# 2_MPC555.net
KiCad netlist of a schematic drawn in Altium Designer
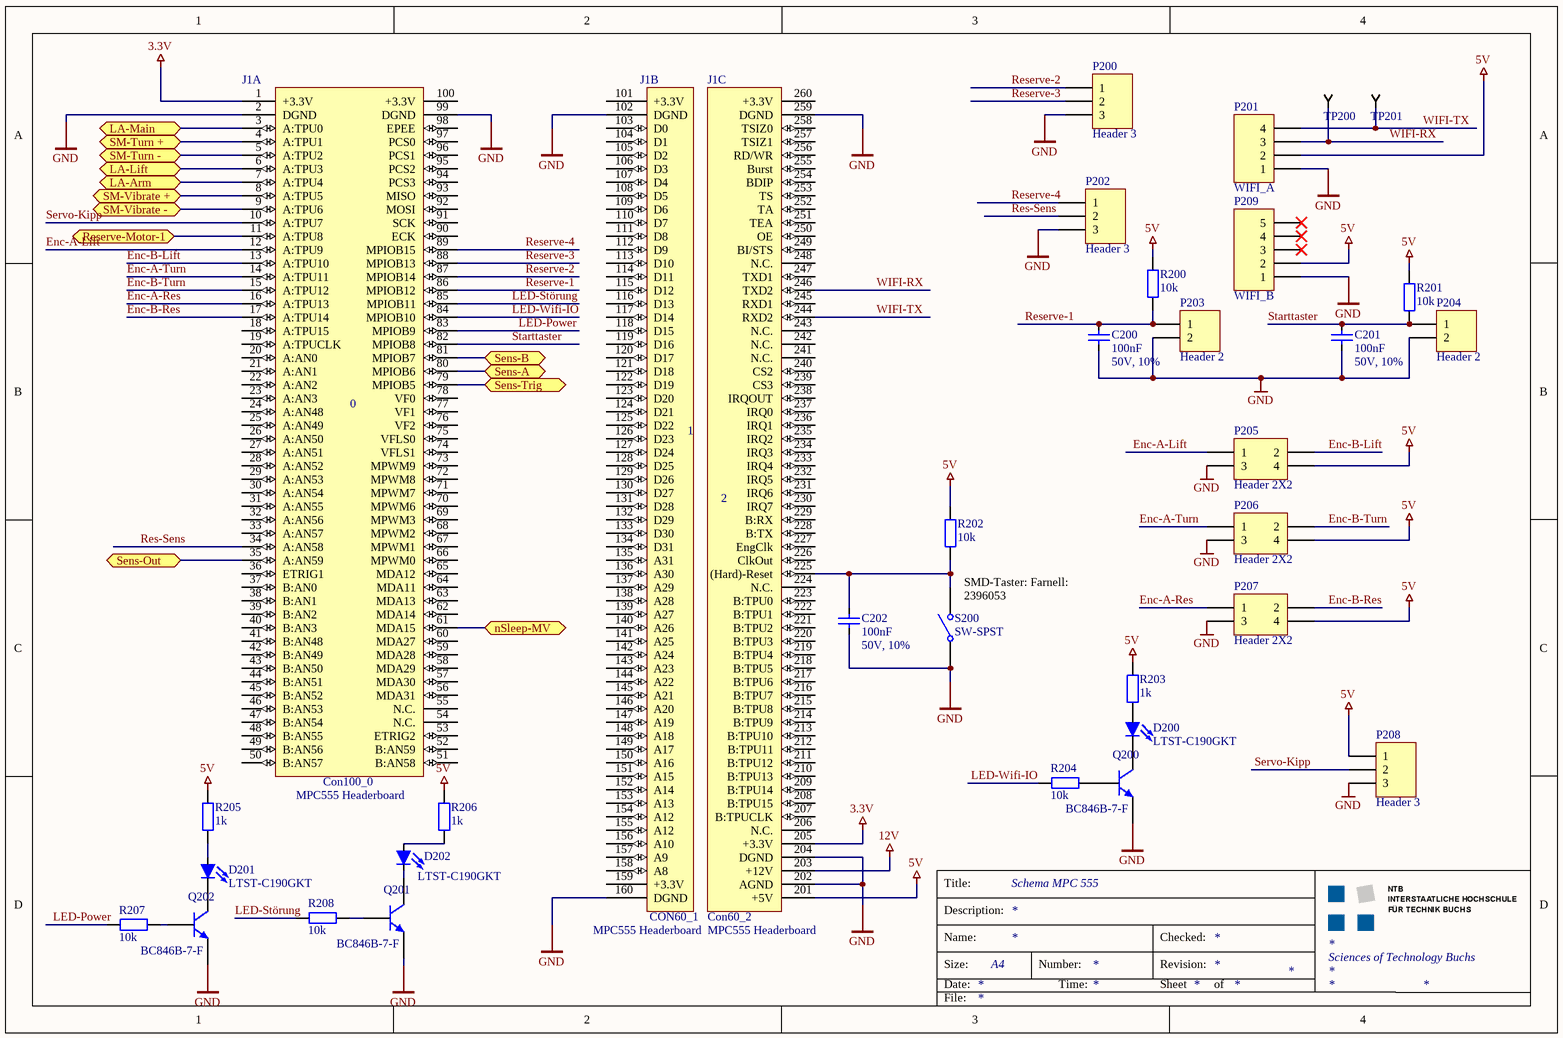
[diagram p0: 2_MPC555.SchDoc]

(export (version "E")
  (design (tool "Eeschema 10.0.6"))
  (components
    (comp (ref "C200")
      (value "100nF")
      (footprint "CAP-0805[2012]")
      (description "100n 50V X7R MLCC 0805 (1608 Metric)")
      (fields (field (name "TOLERANCE") "10%") (field (name "VALADDON") "50V, 10%"))
      (libsource (lib "IR-Sensor") (part "MLCC 0805 100n 50V"))
    )
    (comp (ref "C201")
      (value "100nF")
      (footprint "CAP-0805[2012]")
      (description "100n 50V X7R MLCC 0805 (1608 Metric)")
      (fields (field (name "TOLERANCE") "10%") (field (name "VALADDON") "50V, 10%"))
      (libsource (lib "IR-Sensor") (part "MLCC 0805 100n 50V"))
    )
    (comp (ref "C202")
      (value "100nF")
      (footprint "CAP-0805[2012]")
      (description "100n 50V X7R MLCC 0805 (1608 Metric)")
      (fields (field (name "TOLERANCE") "10%") (field (name "VALADDON") "50V, 10%"))
      (libsource (lib "IR-Sensor") (part "MLCC 0805 100n 50V"))
    )
    (comp (ref "D200")
      (value "LTST-C190GKT")
      (footprint "LED 0603 green")
      (description "LED SMD 0603 green 6mcd")
      (libsource (lib "IR-Sensor") (part "LED Green"))
    )
    (comp (ref "D201")
      (value "LTST-C190GKT")
      (footprint "LED 0603 green")
      (description "LED SMD 0603 green 6mcd")
      (libsource (lib "IR-Sensor") (part "LED Green"))
    )
    (comp (ref "D202")
      (value "LTST-C190GKT")
      (footprint "LED 0603 green")
      (description "LED SMD 0603 green 6mcd")
      (libsource (lib "IR-Sensor") (part "LED Green"))
    )
    (comp (ref "J1")
      (value "MPC555 Headerboard")
      (footprint "MPC555 Headerboard THT")
      (description "NTB MPC555 Headerboard")
      (libsource (lib "ch.ntb.inf.altiumlib_2011-02-10") (part "MPC555 Headerboard"))
    )
    (comp (ref "P200")
      (value "Header 3")
      (footprint "HDR1X3")
      (description "Header, 3-Pin")
      (fields (field (name "PUBLISHER") "Altium Limited"))
      (libsource (lib "Miscellaneous Connectors") (part "Header 3"))
    )
    (comp (ref "P201")
      (value "WIFI_A")
      (footprint "HDR1X4")
      (description "Header, 4-Pin")
      (fields (field (name "PUBLISHER") "Altium Limited"))
      (libsource (lib "Miscellaneous Connectors") (part "Header 4"))
    )
    (comp (ref "P202")
      (value "Header 3")
      (footprint "HDR1X3")
      (description "Header, 3-Pin")
      (fields (field (name "PUBLISHER") "Altium Limited"))
      (libsource (lib "Miscellaneous Connectors") (part "Header 3"))
    )
    (comp (ref "P203")
      (value "Header 2")
      (footprint "HDR1X2")
      (description "Header, 2-Pin")
      (fields (field (name "PUBLISHER") "Altium Limited"))
      (libsource (lib "Miscellaneous Connectors") (part "Header 2"))
    )
    (comp (ref "P204")
      (value "Header 2")
      (footprint "HDR1X2")
      (description "Header, 2-Pin")
      (fields (field (name "PUBLISHER") "Altium Limited"))
      (libsource (lib "Miscellaneous Connectors") (part "Header 2"))
    )
    (comp (ref "P205")
      (value "Header 2X2")
      (footprint "HDR2X2")
      (description "Header, 2-Pin, Dual row")
      (fields (field (name "PUBLISHER") "Altium Limited"))
      (libsource (lib "Miscellaneous Connectors") (part "Header 2X2"))
    )
    (comp (ref "P206")
      (value "Header 2X2")
      (footprint "HDR2X2")
      (description "Header, 2-Pin, Dual row")
      (fields (field (name "PUBLISHER") "Altium Limited"))
      (libsource (lib "Miscellaneous Connectors") (part "Header 2X2"))
    )
    (comp (ref "P207")
      (value "Header 2X2")
      (footprint "HDR2X2")
      (description "Header, 2-Pin, Dual row")
      (fields (field (name "PUBLISHER") "Altium Limited"))
      (libsource (lib "Miscellaneous Connectors") (part "Header 2X2"))
    )
    (comp (ref "P208")
      (value "Header 3")
      (footprint "HDR1X3")
      (description "Header, 3-Pin")
      (fields (field (name "PUBLISHER") "Altium Limited"))
      (libsource (lib "Miscellaneous Connectors") (part "Header 3"))
    )
    (comp (ref "P209")
      (value "WIFI_B")
      (footprint "HDR1X5")
      (description "Header, 5-Pin")
      (fields (field (name "PUBLISHER") "Altium Limited"))
      (libsource (lib "Miscellaneous Connectors") (part "Header 5"))
    )
    (comp (ref "Q200")
      (value "BC846B-7-F")
      (footprint "SOT-23")
      (description "NPN General-purpose Transistor")
      (fields (field (name "MANUFACTURER") "DIODES INC") (field (name "PUBLISHER") "Altium Limited"))
      (libsource (lib "IR-Sensor") (part "BC846B-SOT23"))
    )
    (comp (ref "Q201")
      (value "BC846B-7-F")
      (footprint "SOT-23")
      (description "NPN General-purpose Transistor")
      (fields (field (name "MANUFACTURER") "DIODES INC") (field (name "PUBLISHER") "Altium Limited"))
      (libsource (lib "IR-Sensor") (part "BC846B-SOT23"))
    )
    (comp (ref "Q202")
      (value "BC846B-7-F")
      (footprint "SOT-23")
      (description "NPN General-purpose Transistor")
      (fields (field (name "MANUFACTURER") "DIODES INC") (field (name "PUBLISHER") "Altium Limited"))
      (libsource (lib "IR-Sensor") (part "BC846B-SOT23"))
    )
    (comp (ref "R200")
      (value "10k")
      (footprint "RES-0805[2012]")
      (description "0805 (2013 Metric) 1/10 W 10K 1 Thick Film Chip Resistor")
      (fields (field (name "POWER") "1/10 W") (field (name "TOLERANCE") "1%"))
      (libsource (lib "IR-Sensor") (part "RES 0805"))
    )
    (comp (ref "R201")
      (value "10k")
      (footprint "RES-0805[2012]")
      (description "0805 (2013 Metric) 1/10 W 10K 1 Thick Film Chip Resistor")
      (fields (field (name "POWER") "1/10 W") (field (name "TOLERANCE") "1%"))
      (libsource (lib "IR-Sensor") (part "RES 0805"))
    )
    (comp (ref "R202")
      (value "10k")
      (footprint "RES-0805[2012]")
      (description "0805 (2013 Metric) 1/10 W 10K 1 Thick Film Chip Resistor")
      (fields (field (name "POWER") "1/10 W") (field (name "TOLERANCE") "1%"))
      (libsource (lib "IR-Sensor") (part "RES 0805"))
    )
    (comp (ref "R203")
      (value "1k")
      (footprint "RES-0805[2012]")
      (description "0805 (2013 Metric) 1/10 W 10K 1 Thick Film Chip Resistor")
      (fields (field (name "POWER") "1/10 W") (field (name "TOLERANCE") "1%"))
      (libsource (lib "IR-Sensor") (part "RES 0805"))
    )
    (comp (ref "R204")
      (value "10k")
      (footprint "RES-0805[2012]")
      (description "0805 (2013 Metric) 1/10 W 10K 1 Thick Film Chip Resistor")
      (fields (field (name "POWER") "1/10 W") (field (name "TOLERANCE") "1%"))
      (libsource (lib "IR-Sensor") (part "RES 0805"))
    )
    (comp (ref "R205")
      (value "1k")
      (footprint "RES-0805[2012]")
      (description "0805 (2013 Metric) 1/10 W 10K 1 Thick Film Chip Resistor")
      (fields (field (name "POWER") "1/10 W") (field (name "TOLERANCE") "1%"))
      (libsource (lib "IR-Sensor") (part "RES 0805"))
    )
    (comp (ref "R206")
      (value "1k")
      (footprint "RES-0805[2012]")
      (description "0805 (2013 Metric) 1/10 W 10K 1 Thick Film Chip Resistor")
      (fields (field (name "POWER") "1/10 W") (field (name "TOLERANCE") "1%"))
      (libsource (lib "IR-Sensor") (part "RES 0805"))
    )
    (comp (ref "R207")
      (value "10k")
      (footprint "RES-0805[2012]")
      (description "0805 (2013 Metric) 1/10 W 10K 1 Thick Film Chip Resistor")
      (fields (field (name "POWER") "1/10 W") (field (name "TOLERANCE") "1%"))
      (libsource (lib "IR-Sensor") (part "RES 0805"))
    )
    (comp (ref "R208")
      (value "10k")
      (footprint "RES-0805[2012]")
      (description "0805 (2013 Metric) 1/10 W 10K 1 Thick Film Chip Resistor")
      (fields (field (name "POWER") "1/10 W") (field (name "TOLERANCE") "1%"))
      (libsource (lib "IR-Sensor") (part "RES 0805"))
    )
    (comp (ref "S200")
      (value "SW-SPST")
      (footprint "B3SE-1002P")
      (description "Single-Pole, Single-Throw Switch")
      (fields (field (name "PUBLISHER") "Altium Limited"))
      (libsource (lib "Miscellaneous Devices") (part "SW-SPST"))
    )
    (comp (ref "TP200")
      (value "Testpoint SMD 1206")
      (footprint "TP-SMD-1206")
      (description "Testpoint xSmall")
      (libsource (lib "IR-Sensor") (part "Testpoint SMD 1206"))
    )
    (comp (ref "TP201")
      (value "Testpoint SMD 1206")
      (footprint "TP-SMD-1206")
      (description "Testpoint xSmall")
      (libsource (lib "IR-Sensor") (part "Testpoint SMD 1206"))
    )
  )
  (nets
    (net (code "1") (name "/Enc-A-Lift") (class "Default")
      (node (ref "J1") (pin "12") (pinfunction "A:TPU9_12") (pintype "bidirectional"))
      (node (ref "P205") (pin "1") (pinfunction "1_1") (pintype "passive"))
    )
    (net (code "2") (name "/Enc-A-Res") (class "Default")
      (node (ref "J1") (pin "16") (pinfunction "A:TPU13_16") (pintype "bidirectional"))
      (node (ref "P207") (pin "1") (pinfunction "1_1") (pintype "passive"))
    )
    (net (code "3") (name "/Enc-A-Turn") (class "Default")
      (node (ref "J1") (pin "14") (pinfunction "A:TPU11_14") (pintype "bidirectional"))
      (node (ref "P206") (pin "1") (pinfunction "1_1") (pintype "passive"))
    )
    (net (code "4") (name "/Enc-B-Lift") (class "Default")
      (node (ref "J1") (pin "13") (pinfunction "A:TPU10_13") (pintype "bidirectional"))
      (node (ref "P205") (pin "2") (pinfunction "2_2") (pintype "passive"))
    )
    (net (code "5") (name "/Enc-B-Res") (class "Default")
      (node (ref "J1") (pin "17") (pinfunction "A:TPU14_17") (pintype "bidirectional"))
      (node (ref "P207") (pin "2") (pinfunction "2_2") (pintype "passive"))
    )
    (net (code "6") (name "/Enc-B-Turn") (class "Default")
      (node (ref "J1") (pin "15") (pinfunction "A:TPU12_15") (pintype "bidirectional"))
      (node (ref "P206") (pin "2") (pinfunction "2_2") (pintype "passive"))
    )
    (net (code "7") (name "/LA-Arm") (class "Default")
      (node (ref "J1") (pin "7") (pinfunction "A:TPU4_7") (pintype "bidirectional"))
    )
    (net (code "8") (name "/LA-Lift") (class "Default")
      (node (ref "J1") (pin "6") (pinfunction "A:TPU3_6") (pintype "bidirectional"))
    )
    (net (code "9") (name "/LA-Main") (class "Default")
      (node (ref "J1") (pin "3") (pinfunction "A:TPU0_3") (pintype "bidirectional"))
    )
    (net (code "10") (name "/LED-Power") (class "Default")
      (node (ref "J1") (pin "83") (pinfunction "MPIOB9_83") (pintype "bidirectional"))
      (node (ref "R207") (pin "1") (pinfunction "1_1") (pintype "passive"))
    )
    (net (code "11") (name "/LED-Störung") (class "Default")
      (node (ref "J1") (pin "85") (pinfunction "MPIOB11_85") (pintype "bidirectional"))
      (node (ref "R208") (pin "1") (pinfunction "1_1") (pintype "passive"))
    )
    (net (code "12") (name "/LED-Wifi-IO") (class "Default")
      (node (ref "J1") (pin "84") (pinfunction "MPIOB10_84") (pintype "bidirectional"))
      (node (ref "R204") (pin "1") (pinfunction "1_1") (pintype "passive"))
    )
    (net (code "13") (name "/Res-Sens") (class "Default")
      (node (ref "J1") (pin "34") (pinfunction "A:AN58_34") (pintype "bidirectional"))
      (node (ref "P202") (pin "2") (pinfunction "2_2") (pintype "passive"))
    )
    (net (code "14") (name "/Reserve-1") (class "Default")
      (node (ref "C200") (pin "2") (pinfunction "Neg_2") (pintype "passive"))
      (node (ref "J1") (pin "86") (pinfunction "MPIOB12_86") (pintype "bidirectional"))
      (node (ref "P203") (pin "1") (pinfunction "1_1") (pintype "passive"))
      (node (ref "R200") (pin "1") (pinfunction "1_1") (pintype "passive"))
    )
    (net (code "15") (name "/Reserve-2") (class "Default")
      (node (ref "J1") (pin "87") (pinfunction "MPIOB14_87") (pintype "bidirectional"))
      (node (ref "P200") (pin "1") (pinfunction "1_1") (pintype "passive"))
    )
    (net (code "16") (name "/Reserve-3") (class "Default")
      (node (ref "J1") (pin "88") (pinfunction "MPIOB13_88") (pintype "bidirectional"))
      (node (ref "P200") (pin "2") (pinfunction "2_2") (pintype "passive"))
    )
    (net (code "17") (name "/Reserve-4") (class "Default")
      (node (ref "J1") (pin "89") (pinfunction "MPIOB15_89") (pintype "bidirectional"))
      (node (ref "P202") (pin "1") (pinfunction "1_1") (pintype "passive"))
    )
    (net (code "18") (name "/Reserve-Motor-1") (class "Default")
      (node (ref "J1") (pin "11") (pinfunction "A:TPU8_11") (pintype "bidirectional"))
    )
    (net (code "19") (name "/SM-Turn +") (class "Default")
      (node (ref "J1") (pin "4") (pinfunction "A:TPU1_4") (pintype "bidirectional"))
    )
    (net (code "20") (name "/SM-Turn -") (class "Default")
      (node (ref "J1") (pin "5") (pinfunction "A:TPU2_5") (pintype "bidirectional"))
    )
    (net (code "21") (name "/SM-Vibrate +") (class "Default")
      (node (ref "J1") (pin "8") (pinfunction "A:TPU5_8") (pintype "bidirectional"))
    )
    (net (code "22") (name "/SM-Vibrate -") (class "Default")
      (node (ref "J1") (pin "9") (pinfunction "A:TPU6_9") (pintype "bidirectional"))
    )
    (net (code "23") (name "/Sens-A") (class "Default")
      (node (ref "J1") (pin "80") (pinfunction "MPIOB6_80") (pintype "bidirectional"))
    )
    (net (code "24") (name "/Sens-B") (class "Default")
      (node (ref "J1") (pin "81") (pinfunction "MPIOB7_81") (pintype "bidirectional"))
    )
    (net (code "25") (name "/Sens-Out") (class "Default")
      (node (ref "J1") (pin "35") (pinfunction "A:AN59_35") (pintype "bidirectional"))
    )
    (net (code "26") (name "/Sens-Trig") (class "Default")
      (node (ref "J1") (pin "79") (pinfunction "MPIOB5_79") (pintype "bidirectional"))
    )
    (net (code "27") (name "/Servo-Kipp") (class "Default")
      (node (ref "J1") (pin "10") (pinfunction "A:TPU7_10") (pintype "bidirectional"))
      (node (ref "P208") (pin "2") (pinfunction "2_2") (pintype "passive"))
    )
    (net (code "28") (name "/Starttaster") (class "Default")
      (node (ref "C201") (pin "2") (pinfunction "Neg_2") (pintype "passive"))
      (node (ref "J1") (pin "82") (pinfunction "MPIOB8_82") (pintype "bidirectional"))
      (node (ref "P204") (pin "1") (pinfunction "1_1") (pintype "passive"))
      (node (ref "R201") (pin "1") (pinfunction "1_1") (pintype "passive"))
    )
    (net (code "29") (name "/WIFI-RX") (class "Default")
      (node (ref "J1") (pin "246") (pinfunction "TXD2_246") (pintype "bidirectional"))
      (node (ref "P201") (pin "3") (pinfunction "3_3") (pintype "passive"))
      (node (ref "TP200") (pin "1") (pinfunction "0_1") (pintype "passive"))
    )
    (net (code "30") (name "/WIFI-TX") (class "Default")
      (node (ref "J1") (pin "244") (pinfunction "RXD2_244") (pintype "bidirectional"))
      (node (ref "P201") (pin "4") (pinfunction "4_4") (pintype "passive"))
      (node (ref "TP201") (pin "1") (pinfunction "0_1") (pintype "passive"))
    )
    (net (code "31") (name "/nSleep-MV") (class "Default")
      (node (ref "J1") (pin "61") (pinfunction "MDA15_61") (pintype "bidirectional"))
    )
    (net (code "32") (name "3.3V") (class "Default")
      (node (ref "J1") (pin "1") (pinfunction "+3.3V_1") (pintype "power_in"))
      (node (ref "J1") (pin "205") (pinfunction "+3.3V_205") (pintype "power_in"))
    )
    (net (code "33") (name "5V") (class "Default")
      (node (ref "J1") (pin "201") (pinfunction "+5V_201") (pintype "power_in"))
      (node (ref "P201") (pin "2") (pinfunction "2_2") (pintype "passive"))
      (node (ref "P205") (pin "4") (pinfunction "4_4") (pintype "passive"))
      (node (ref "P206") (pin "4") (pinfunction "4_4") (pintype "passive"))
      (node (ref "P207") (pin "4") (pinfunction "4_4") (pintype "passive"))
      (node (ref "P208") (pin "1") (pinfunction "1_1") (pintype "passive"))
      (node (ref "P209") (pin "2") (pinfunction "2_2") (pintype "passive"))
      (node (ref "R200") (pin "2") (pinfunction "2_2") (pintype "passive"))
      (node (ref "R201") (pin "2") (pinfunction "2_2") (pintype "passive"))
      (node (ref "R202") (pin "2") (pinfunction "2_2") (pintype "passive"))
      (node (ref "R203") (pin "2") (pinfunction "2_2") (pintype "passive"))
      (node (ref "R205") (pin "2") (pinfunction "2_2") (pintype "passive"))
      (node (ref "R206") (pin "2") (pinfunction "2_2") (pintype "passive"))
    )
    (net (code "34") (name "12V") (class "Default")
      (node (ref "J1") (pin "203") (pinfunction "+12V_203") (pintype "power_in"))
    )
    (net (code "35") (name "GND") (class "Default")
      (node (ref "C200") (pin "1") (pinfunction "Pos_1") (pintype "passive"))
      (node (ref "C201") (pin "1") (pinfunction "Pos_1") (pintype "passive"))
      (node (ref "C202") (pin "1") (pinfunction "Pos_1") (pintype "passive"))
      (node (ref "J1") (pin "102") (pinfunction "DGND_102") (pintype "power_in"))
      (node (ref "J1") (pin "160") (pinfunction "DGND_160") (pintype "power_in"))
      (node (ref "J1") (pin "2") (pinfunction "DGND_2") (pintype "power_in"))
      (node (ref "J1") (pin "202") (pinfunction "AGND_202") (pintype "power_in"))
      (node (ref "J1") (pin "204") (pinfunction "DGND_204") (pintype "power_in"))
      (node (ref "J1") (pin "259") (pinfunction "DGND_259") (pintype "power_in"))
      (node (ref "J1") (pin "99") (pinfunction "DGND_99") (pintype "power_in"))
      (node (ref "P200") (pin "3") (pinfunction "3_3") (pintype "passive"))
      (node (ref "P201") (pin "1") (pinfunction "1_1") (pintype "passive"))
      (node (ref "P202") (pin "3") (pinfunction "3_3") (pintype "passive"))
      (node (ref "P203") (pin "2") (pinfunction "2_2") (pintype "passive"))
      (node (ref "P204") (pin "2") (pinfunction "2_2") (pintype "passive"))
      (node (ref "P205") (pin "3") (pinfunction "3_3") (pintype "passive"))
      (node (ref "P206") (pin "3") (pinfunction "3_3") (pintype "passive"))
      (node (ref "P207") (pin "3") (pinfunction "3_3") (pintype "passive"))
      (node (ref "P208") (pin "3") (pinfunction "3_3") (pintype "passive"))
      (node (ref "P209") (pin "1") (pinfunction "1_1") (pintype "passive"))
      (node (ref "Q200") (pin "2") (pinfunction "E_2") (pintype "passive"))
      (node (ref "Q201") (pin "2") (pinfunction "E_2") (pintype "passive"))
      (node (ref "Q202") (pin "2") (pinfunction "E_2") (pintype "passive"))
      (node (ref "S200") (pin "1") (pinfunction "COMMON_1") (pintype "passive"))
    )
    (net (code "36") (name "Net-(C202-Neg)") (class "Default")
      (node (ref "C202") (pin "2") (pinfunction "Neg_2") (pintype "passive"))
      (node (ref "J1") (pin "225") (pinfunction "(Hard)-Reset_225") (pintype "bidirectional"))
      (node (ref "R202") (pin "1") (pinfunction "1_1") (pintype "passive"))
      (node (ref "S200") (pin "2") (pinfunction "NO_2") (pintype "passive"))
    )
    (net (code "37") (name "Net-(D200-A)") (class "Default")
      (node (ref "D200") (pin "2") (pinfunction "A_2") (pintype "passive"))
      (node (ref "R203") (pin "1") (pinfunction "1_1") (pintype "passive"))
    )
    (net (code "38") (name "Net-(D200-K)") (class "Default")
      (node (ref "D200") (pin "1") (pinfunction "K_1") (pintype "passive"))
      (node (ref "Q200") (pin "3") (pinfunction "C_3") (pintype "passive"))
    )
    (net (code "39") (name "Net-(D201-A)") (class "Default")
      (node (ref "D201") (pin "2") (pinfunction "A_2") (pintype "passive"))
      (node (ref "R205") (pin "1") (pinfunction "1_1") (pintype "passive"))
    )
    (net (code "40") (name "Net-(D201-K)") (class "Default")
      (node (ref "D201") (pin "1") (pinfunction "K_1") (pintype "passive"))
      (node (ref "Q202") (pin "3") (pinfunction "C_3") (pintype "passive"))
    )
    (net (code "41") (name "Net-(D202-A)") (class "Default")
      (node (ref "D202") (pin "2") (pinfunction "A_2") (pintype "passive"))
      (node (ref "R206") (pin "1") (pinfunction "1_1") (pintype "passive"))
    )
    (net (code "42") (name "Net-(D202-K)") (class "Default")
      (node (ref "D202") (pin "1") (pinfunction "K_1") (pintype "passive"))
      (node (ref "Q201") (pin "3") (pinfunction "C_3") (pintype "passive"))
    )
    (net (code "43") (name "Net-(Q200-B)") (class "Default")
      (node (ref "Q200") (pin "1") (pinfunction "B_1") (pintype "passive"))
      (node (ref "R204") (pin "2") (pinfunction "2_2") (pintype "passive"))
    )
    (net (code "44") (name "Net-(Q201-B)") (class "Default")
      (node (ref "Q201") (pin "1") (pinfunction "B_1") (pintype "passive"))
      (node (ref "R208") (pin "2") (pinfunction "2_2") (pintype "passive"))
    )
    (net (code "45") (name "Net-(Q202-B)") (class "Default")
      (node (ref "Q202") (pin "1") (pinfunction "B_1") (pintype "passive"))
      (node (ref "R207") (pin "2") (pinfunction "2_2") (pintype "passive"))
    )
    (net (code "46") (name "unconnected-(J1A-+3.3V-Pad100)") (class "Default")
      (node (ref "J1") (pin "100") (pinfunction "+3.3V_100") (pintype "power_in"))
    )
    (net (code "47") (name "unconnected-(J1A-A:AN0-Pad20)") (class "Default")
      (node (ref "J1") (pin "20") (pinfunction "A:AN0_20") (pintype "bidirectional"))
    )
    (net (code "48") (name "unconnected-(J1A-A:AN1-Pad21)") (class "Default")
      (node (ref "J1") (pin "21") (pinfunction "A:AN1_21") (pintype "bidirectional"))
    )
    (net (code "49") (name "unconnected-(J1A-A:AN2-Pad22)") (class "Default")
      (node (ref "J1") (pin "22") (pinfunction "A:AN2_22") (pintype "bidirectional"))
    )
    (net (code "50") (name "unconnected-(J1A-A:AN3-Pad23)") (class "Default")
      (node (ref "J1") (pin "23") (pinfunction "A:AN3_23") (pintype "bidirectional"))
    )
    (net (code "51") (name "unconnected-(J1A-A:AN48-Pad24)") (class "Default")
      (node (ref "J1") (pin "24") (pinfunction "A:AN48_24") (pintype "bidirectional"))
    )
    (net (code "52") (name "unconnected-(J1A-A:AN49-Pad25)") (class "Default")
      (node (ref "J1") (pin "25") (pinfunction "A:AN49_25") (pintype "bidirectional"))
    )
    (net (code "53") (name "unconnected-(J1A-A:AN50-Pad26)") (class "Default")
      (node (ref "J1") (pin "26") (pinfunction "A:AN50_26") (pintype "bidirectional"))
    )
    (net (code "54") (name "unconnected-(J1A-A:AN51-Pad27)") (class "Default")
      (node (ref "J1") (pin "27") (pinfunction "A:AN51_27") (pintype "bidirectional"))
    )
    (net (code "55") (name "unconnected-(J1A-A:AN52-Pad28)") (class "Default")
      (node (ref "J1") (pin "28") (pinfunction "A:AN52_28") (pintype "bidirectional"))
    )
    (net (code "56") (name "unconnected-(J1A-A:AN53-Pad29)") (class "Default")
      (node (ref "J1") (pin "29") (pinfunction "A:AN53_29") (pintype "bidirectional"))
    )
    (net (code "57") (name "unconnected-(J1A-A:AN54-Pad30)") (class "Default")
      (node (ref "J1") (pin "30") (pinfunction "A:AN54_30") (pintype "bidirectional"))
    )
    (net (code "58") (name "unconnected-(J1A-A:AN55-Pad31)") (class "Default")
      (node (ref "J1") (pin "31") (pinfunction "A:AN55_31") (pintype "bidirectional"))
    )
    (net (code "59") (name "unconnected-(J1A-A:AN56-Pad32)") (class "Default")
      (node (ref "J1") (pin "32") (pinfunction "A:AN56_32") (pintype "bidirectional"))
    )
    (net (code "60") (name "unconnected-(J1A-A:AN57-Pad33)") (class "Default")
      (node (ref "J1") (pin "33") (pinfunction "A:AN57_33") (pintype "bidirectional"))
    )
    (net (code "61") (name "unconnected-(J1A-A:TPU15-Pad18)") (class "Default")
      (node (ref "J1") (pin "18") (pinfunction "A:TPU15_18") (pintype "bidirectional"))
    )
    (net (code "62") (name "unconnected-(J1A-A:TPUCLK-Pad19)") (class "Default")
      (node (ref "J1") (pin "19") (pinfunction "A:TPUCLK_19") (pintype "bidirectional"))
    )
    (net (code "63") (name "unconnected-(J1A-B:AN0-Pad37)") (class "Default")
      (node (ref "J1") (pin "37") (pinfunction "B:AN0_37") (pintype "bidirectional"))
    )
    (net (code "64") (name "unconnected-(J1A-B:AN1-Pad38)") (class "Default")
      (node (ref "J1") (pin "38") (pinfunction "B:AN1_38") (pintype "bidirectional"))
    )
    (net (code "65") (name "unconnected-(J1A-B:AN2-Pad39)") (class "Default")
      (node (ref "J1") (pin "39") (pinfunction "B:AN2_39") (pintype "bidirectional"))
    )
    (net (code "66") (name "unconnected-(J1A-B:AN3-Pad40)") (class "Default")
      (node (ref "J1") (pin "40") (pinfunction "B:AN3_40") (pintype "bidirectional"))
    )
    (net (code "67") (name "unconnected-(J1A-B:AN48-Pad41)") (class "Default")
      (node (ref "J1") (pin "41") (pinfunction "B:AN48_41") (pintype "bidirectional"))
    )
    (net (code "68") (name "unconnected-(J1A-B:AN49-Pad42)") (class "Default")
      (node (ref "J1") (pin "42") (pinfunction "B:AN49_42") (pintype "bidirectional"))
    )
    (net (code "69") (name "unconnected-(J1A-B:AN50-Pad43)") (class "Default")
      (node (ref "J1") (pin "43") (pinfunction "B:AN50_43") (pintype "bidirectional"))
    )
    (net (code "70") (name "unconnected-(J1A-B:AN51-Pad44)") (class "Default")
      (node (ref "J1") (pin "44") (pinfunction "B:AN51_44") (pintype "bidirectional"))
    )
    (net (code "71") (name "unconnected-(J1A-B:AN52-Pad45)") (class "Default")
      (node (ref "J1") (pin "45") (pinfunction "B:AN52_45") (pintype "bidirectional"))
    )
    (net (code "72") (name "unconnected-(J1A-B:AN53-Pad46)") (class "Default")
      (node (ref "J1") (pin "46") (pinfunction "B:AN53_46") (pintype "bidirectional"))
    )
    (net (code "73") (name "unconnected-(J1A-B:AN54-Pad47)") (class "Default")
      (node (ref "J1") (pin "47") (pinfunction "B:AN54_47") (pintype "bidirectional"))
    )
    (net (code "74") (name "unconnected-(J1A-B:AN55-Pad48)") (class "Default")
      (node (ref "J1") (pin "48") (pinfunction "B:AN55_48") (pintype "bidirectional"))
    )
    (net (code "75") (name "unconnected-(J1A-B:AN56-Pad49)") (class "Default")
      (node (ref "J1") (pin "49") (pinfunction "B:AN56_49") (pintype "bidirectional"))
    )
    (net (code "76") (name "unconnected-(J1A-B:AN57-Pad50)") (class "Default")
      (node (ref "J1") (pin "50") (pinfunction "B:AN57_50") (pintype "bidirectional"))
    )
    (net (code "77") (name "unconnected-(J1A-B:AN58-Pad51)") (class "Default")
      (node (ref "J1") (pin "51") (pinfunction "B:AN58_51") (pintype "bidirectional"))
    )
    (net (code "78") (name "unconnected-(J1A-B:AN59-Pad52)") (class "Default")
      (node (ref "J1") (pin "52") (pinfunction "B:AN59_52") (pintype "bidirectional"))
    )
    (net (code "79") (name "unconnected-(J1A-ECK-Pad90)") (class "Default")
      (node (ref "J1") (pin "90") (pinfunction "ECK_90") (pintype "bidirectional"))
    )
    (net (code "80") (name "unconnected-(J1A-EPEE-Pad98)") (class "Default")
      (node (ref "J1") (pin "98") (pinfunction "EPEE_98") (pintype "bidirectional"))
    )
    (net (code "81") (name "unconnected-(J1A-ETRIG1-Pad36)") (class "Default")
      (node (ref "J1") (pin "36") (pinfunction "ETRIG1_36") (pintype "bidirectional"))
    )
    (net (code "82") (name "unconnected-(J1A-ETRIG2-Pad53)") (class "Default")
      (node (ref "J1") (pin "53") (pinfunction "ETRIG2_53") (pintype "bidirectional"))
    )
    (net (code "83") (name "unconnected-(J1A-MDA11-Pad64)") (class "Default")
      (node (ref "J1") (pin "64") (pinfunction "MDA11_64") (pintype "bidirectional"))
    )
    (net (code "84") (name "unconnected-(J1A-MDA12-Pad65)") (class "Default")
      (node (ref "J1") (pin "65") (pinfunction "MDA12_65") (pintype "bidirectional"))
    )
    (net (code "85") (name "unconnected-(J1A-MDA13-Pad63)") (class "Default")
      (node (ref "J1") (pin "63") (pinfunction "MDA13_63") (pintype "bidirectional"))
    )
    (net (code "86") (name "unconnected-(J1A-MDA14-Pad62)") (class "Default")
      (node (ref "J1") (pin "62") (pinfunction "MDA14_62") (pintype "bidirectional"))
    )
    (net (code "87") (name "unconnected-(J1A-MDA27-Pad60)") (class "Default")
      (node (ref "J1") (pin "60") (pinfunction "MDA27_60") (pintype "bidirectional"))
    )
    (net (code "88") (name "unconnected-(J1A-MDA28-Pad59)") (class "Default")
      (node (ref "J1") (pin "59") (pinfunction "MDA28_59") (pintype "bidirectional"))
    )
    (net (code "89") (name "unconnected-(J1A-MDA29-Pad58)") (class "Default")
      (node (ref "J1") (pin "58") (pinfunction "MDA29_58") (pintype "bidirectional"))
    )
    (net (code "90") (name "unconnected-(J1A-MDA30-Pad57)") (class "Default")
      (node (ref "J1") (pin "57") (pinfunction "MDA30_57") (pintype "bidirectional"))
    )
    (net (code "91") (name "unconnected-(J1A-MDA31-Pad56)") (class "Default")
      (node (ref "J1") (pin "56") (pinfunction "MDA31_56") (pintype "bidirectional"))
    )
    (net (code "92") (name "unconnected-(J1A-MISO-Pad93)") (class "Default")
      (node (ref "J1") (pin "93") (pinfunction "MISO_93") (pintype "bidirectional"))
    )
    (net (code "93") (name "unconnected-(J1A-MOSI-Pad92)") (class "Default")
      (node (ref "J1") (pin "92") (pinfunction "MOSI_92") (pintype "bidirectional"))
    )
    (net (code "94") (name "unconnected-(J1A-MPWM0-Pad66)") (class "Default")
      (node (ref "J1") (pin "66") (pinfunction "MPWM0_66") (pintype "bidirectional"))
    )
    (net (code "95") (name "unconnected-(J1A-MPWM1-Pad67)") (class "Default")
      (node (ref "J1") (pin "67") (pinfunction "MPWM1_67") (pintype "bidirectional"))
    )
    (net (code "96") (name "unconnected-(J1A-MPWM2-Pad68)") (class "Default")
      (node (ref "J1") (pin "68") (pinfunction "MPWM2_68") (pintype "bidirectional"))
    )
    (net (code "97") (name "unconnected-(J1A-MPWM3-Pad69)") (class "Default")
      (node (ref "J1") (pin "69") (pinfunction "MPWM3_69") (pintype "bidirectional"))
    )
    (net (code "98") (name "unconnected-(J1A-MPWM6-Pad70)") (class "Default")
      (node (ref "J1") (pin "70") (pinfunction "MPWM6_70") (pintype "bidirectional"))
    )
    (net (code "99") (name "unconnected-(J1A-MPWM7-Pad71)") (class "Default")
      (node (ref "J1") (pin "71") (pinfunction "MPWM7_71") (pintype "bidirectional"))
    )
    (net (code "100") (name "unconnected-(J1A-MPWM8-Pad72)") (class "Default")
      (node (ref "J1") (pin "72") (pinfunction "MPWM8_72") (pintype "bidirectional"))
    )
    (net (code "101") (name "unconnected-(J1A-MPWM9-Pad73)") (class "Default")
      (node (ref "J1") (pin "73") (pinfunction "MPWM9_73") (pintype "bidirectional"))
    )
    (net (code "102") (name "unconnected-(J1A-N.C.-Pad54)") (class "Default")
      (node (ref "J1") (pin "54") (pinfunction "N.C._54") (pintype "tri_state"))
    )
    (net (code "103") (name "unconnected-(J1A-N.C.-Pad55)") (class "Default")
      (node (ref "J1") (pin "55") (pinfunction "N.C._55") (pintype "tri_state"))
    )
    (net (code "104") (name "unconnected-(J1A-PCS0-Pad97)") (class "Default")
      (node (ref "J1") (pin "97") (pinfunction "PCS0_97") (pintype "bidirectional"))
    )
    (net (code "105") (name "unconnected-(J1A-PCS1-Pad96)") (class "Default")
      (node (ref "J1") (pin "96") (pinfunction "PCS1_96") (pintype "bidirectional"))
    )
    (net (code "106") (name "unconnected-(J1A-PCS2-Pad95)") (class "Default")
      (node (ref "J1") (pin "95") (pinfunction "PCS2_95") (pintype "bidirectional"))
    )
    (net (code "107") (name "unconnected-(J1A-PCS3-Pad94)") (class "Default")
      (node (ref "J1") (pin "94") (pinfunction "PCS3_94") (pintype "bidirectional"))
    )
    (net (code "108") (name "unconnected-(J1A-SCK-Pad91)") (class "Default")
      (node (ref "J1") (pin "91") (pinfunction "SCK_91") (pintype "bidirectional"))
    )
    (net (code "109") (name "unconnected-(J1A-VF0-Pad78)") (class "Default")
      (node (ref "J1") (pin "78") (pinfunction "VF0_78") (pintype "bidirectional"))
    )
    (net (code "110") (name "unconnected-(J1A-VF1-Pad77)") (class "Default")
      (node (ref "J1") (pin "77") (pinfunction "VF1_77") (pintype "bidirectional"))
    )
    (net (code "111") (name "unconnected-(J1A-VF2-Pad76)") (class "Default")
      (node (ref "J1") (pin "76") (pinfunction "VF2_76") (pintype "bidirectional"))
    )
    (net (code "112") (name "unconnected-(J1A-VFLS0-Pad75)") (class "Default")
      (node (ref "J1") (pin "75") (pinfunction "VFLS0_75") (pintype "bidirectional"))
    )
    (net (code "113") (name "unconnected-(J1A-VFLS1-Pad74)") (class "Default")
      (node (ref "J1") (pin "74") (pinfunction "VFLS1_74") (pintype "bidirectional"))
    )
    (net (code "114") (name "unconnected-(J1B-+3.3V-Pad101)") (class "Default")
      (node (ref "J1") (pin "101") (pinfunction "+3.3V_101") (pintype "power_in"))
    )
    (net (code "115") (name "unconnected-(J1B-+3.3V-Pad159)") (class "Default")
      (node (ref "J1") (pin "159") (pinfunction "+3.3V_159") (pintype "power_in"))
    )
    (net (code "116") (name "unconnected-(J1B-A8-Pad158)") (class "Default")
      (node (ref "J1") (pin "158") (pinfunction "A8_158") (pintype "bidirectional"))
    )
    (net (code "117") (name "unconnected-(J1B-A9-Pad157)") (class "Default")
      (node (ref "J1") (pin "157") (pinfunction "A9_157") (pintype "bidirectional"))
    )
    (net (code "118") (name "unconnected-(J1B-A10-Pad156)") (class "Default")
      (node (ref "J1") (pin "156") (pinfunction "A10_156") (pintype "bidirectional"))
    )
    (net (code "119") (name "unconnected-(J1B-A12-Pad154)") (class "Default")
      (node (ref "J1") (pin "154") (pinfunction "A12_154") (pintype "bidirectional"))
    )
    (net (code "120") (name "unconnected-(J1B-A12-Pad155)") (class "Default")
      (node (ref "J1") (pin "155") (pinfunction "A12_155") (pintype "bidirectional"))
    )
    (net (code "121") (name "unconnected-(J1B-A13-Pad153)") (class "Default")
      (node (ref "J1") (pin "153") (pinfunction "A13_153") (pintype "bidirectional"))
    )
    (net (code "122") (name "unconnected-(J1B-A14-Pad152)") (class "Default")
      (node (ref "J1") (pin "152") (pinfunction "A14_152") (pintype "bidirectional"))
    )
    (net (code "123") (name "unconnected-(J1B-A15-Pad151)") (class "Default")
      (node (ref "J1") (pin "151") (pinfunction "A15_151") (pintype "bidirectional"))
    )
    (net (code "124") (name "unconnected-(J1B-A16-Pad150)") (class "Default")
      (node (ref "J1") (pin "150") (pinfunction "A16_150") (pintype "bidirectional"))
    )
    (net (code "125") (name "unconnected-(J1B-A17-Pad149)") (class "Default")
      (node (ref "J1") (pin "149") (pinfunction "A17_149") (pintype "bidirectional"))
    )
    (net (code "126") (name "unconnected-(J1B-A18-Pad148)") (class "Default")
      (node (ref "J1") (pin "148") (pinfunction "A18_148") (pintype "bidirectional"))
    )
    (net (code "127") (name "unconnected-(J1B-A19-Pad147)") (class "Default")
      (node (ref "J1") (pin "147") (pinfunction "A19_147") (pintype "bidirectional"))
    )
    (net (code "128") (name "unconnected-(J1B-A20-Pad146)") (class "Default")
      (node (ref "J1") (pin "146") (pinfunction "A20_146") (pintype "bidirectional"))
    )
    (net (code "129") (name "unconnected-(J1B-A21-Pad145)") (class "Default")
      (node (ref "J1") (pin "145") (pinfunction "A21_145") (pintype "bidirectional"))
    )
    (net (code "130") (name "unconnected-(J1B-A22-Pad144)") (class "Default")
      (node (ref "J1") (pin "144") (pinfunction "A22_144") (pintype "bidirectional"))
    )
    (net (code "131") (name "unconnected-(J1B-A23-Pad143)") (class "Default")
      (node (ref "J1") (pin "143") (pinfunction "A23_143") (pintype "bidirectional"))
    )
    (net (code "132") (name "unconnected-(J1B-A24-Pad142)") (class "Default")
      (node (ref "J1") (pin "142") (pinfunction "A24_142") (pintype "bidirectional"))
    )
    (net (code "133") (name "unconnected-(J1B-A25-Pad141)") (class "Default")
      (node (ref "J1") (pin "141") (pinfunction "A25_141") (pintype "bidirectional"))
    )
    (net (code "134") (name "unconnected-(J1B-A26-Pad140)") (class "Default")
      (node (ref "J1") (pin "140") (pinfunction "A26_140") (pintype "bidirectional"))
    )
    (net (code "135") (name "unconnected-(J1B-A27-Pad139)") (class "Default")
      (node (ref "J1") (pin "139") (pinfunction "A27_139") (pintype "bidirectional"))
    )
    (net (code "136") (name "unconnected-(J1B-A28-Pad138)") (class "Default")
      (node (ref "J1") (pin "138") (pinfunction "A28_138") (pintype "bidirectional"))
    )
    (net (code "137") (name "unconnected-(J1B-A29-Pad137)") (class "Default")
      (node (ref "J1") (pin "137") (pinfunction "A29_137") (pintype "bidirectional"))
    )
    (net (code "138") (name "unconnected-(J1B-A30-Pad136)") (class "Default")
      (node (ref "J1") (pin "136") (pinfunction "A30_136") (pintype "bidirectional"))
    )
    (net (code "139") (name "unconnected-(J1B-A31-Pad135)") (class "Default")
      (node (ref "J1") (pin "135") (pinfunction "A31_135") (pintype "bidirectional"))
    )
    (net (code "140") (name "unconnected-(J1B-D0-Pad103)") (class "Default")
      (node (ref "J1") (pin "103") (pinfunction "D0_103") (pintype "bidirectional"))
    )
    (net (code "141") (name "unconnected-(J1B-D1-Pad104)") (class "Default")
      (node (ref "J1") (pin "104") (pinfunction "D1_104") (pintype "bidirectional"))
    )
    (net (code "142") (name "unconnected-(J1B-D2-Pad105)") (class "Default")
      (node (ref "J1") (pin "105") (pinfunction "D2_105") (pintype "bidirectional"))
    )
    (net (code "143") (name "unconnected-(J1B-D3-Pad106)") (class "Default")
      (node (ref "J1") (pin "106") (pinfunction "D3_106") (pintype "bidirectional"))
    )
    (net (code "144") (name "unconnected-(J1B-D4-Pad107)") (class "Default")
      (node (ref "J1") (pin "107") (pinfunction "D4_107") (pintype "bidirectional"))
    )
    (net (code "145") (name "unconnected-(J1B-D5-Pad108)") (class "Default")
      (node (ref "J1") (pin "108") (pinfunction "D5_108") (pintype "bidirectional"))
    )
    (net (code "146") (name "unconnected-(J1B-D6-Pad109)") (class "Default")
      (node (ref "J1") (pin "109") (pinfunction "D6_109") (pintype "bidirectional"))
    )
    (net (code "147") (name "unconnected-(J1B-D7-Pad110)") (class "Default")
      (node (ref "J1") (pin "110") (pinfunction "D7_110") (pintype "bidirectional"))
    )
    (net (code "148") (name "unconnected-(J1B-D8-Pad111)") (class "Default")
      (node (ref "J1") (pin "111") (pinfunction "D8_111") (pintype "bidirectional"))
    )
    (net (code "149") (name "unconnected-(J1B-D9-Pad112)") (class "Default")
      (node (ref "J1") (pin "112") (pinfunction "D9_112") (pintype "bidirectional"))
    )
    (net (code "150") (name "unconnected-(J1B-D10-Pad113)") (class "Default")
      (node (ref "J1") (pin "113") (pinfunction "D10_113") (pintype "bidirectional"))
    )
    (net (code "151") (name "unconnected-(J1B-D11-Pad114)") (class "Default")
      (node (ref "J1") (pin "114") (pinfunction "D11_114") (pintype "bidirectional"))
    )
    (net (code "152") (name "unconnected-(J1B-D12-Pad115)") (class "Default")
      (node (ref "J1") (pin "115") (pinfunction "D12_115") (pintype "bidirectional"))
    )
    (net (code "153") (name "unconnected-(J1B-D13-Pad116)") (class "Default")
      (node (ref "J1") (pin "116") (pinfunction "D13_116") (pintype "bidirectional"))
    )
    (net (code "154") (name "unconnected-(J1B-D14-Pad117)") (class "Default")
      (node (ref "J1") (pin "117") (pinfunction "D14_117") (pintype "bidirectional"))
    )
    (net (code "155") (name "unconnected-(J1B-D15-Pad118)") (class "Default")
      (node (ref "J1") (pin "118") (pinfunction "D15_118") (pintype "bidirectional"))
    )
    (net (code "156") (name "unconnected-(J1B-D16-Pad119)") (class "Default")
      (node (ref "J1") (pin "119") (pinfunction "D16_119") (pintype "bidirectional"))
    )
    (net (code "157") (name "unconnected-(J1B-D17-Pad120)") (class "Default")
      (node (ref "J1") (pin "120") (pinfunction "D17_120") (pintype "bidirectional"))
    )
    (net (code "158") (name "unconnected-(J1B-D18-Pad121)") (class "Default")
      (node (ref "J1") (pin "121") (pinfunction "D18_121") (pintype "bidirectional"))
    )
    (net (code "159") (name "unconnected-(J1B-D19-Pad122)") (class "Default")
      (node (ref "J1") (pin "122") (pinfunction "D19_122") (pintype "bidirectional"))
    )
    (net (code "160") (name "unconnected-(J1B-D20-Pad123)") (class "Default")
      (node (ref "J1") (pin "123") (pinfunction "D20_123") (pintype "bidirectional"))
    )
    (net (code "161") (name "unconnected-(J1B-D21-Pad124)") (class "Default")
      (node (ref "J1") (pin "124") (pinfunction "D21_124") (pintype "bidirectional"))
    )
    (net (code "162") (name "unconnected-(J1B-D22-Pad125)") (class "Default")
      (node (ref "J1") (pin "125") (pinfunction "D22_125") (pintype "bidirectional"))
    )
    (net (code "163") (name "unconnected-(J1B-D23-Pad126)") (class "Default")
      (node (ref "J1") (pin "126") (pinfunction "D23_126") (pintype "bidirectional"))
    )
    (net (code "164") (name "unconnected-(J1B-D24-Pad127)") (class "Default")
      (node (ref "J1") (pin "127") (pinfunction "D24_127") (pintype "bidirectional"))
    )
    (net (code "165") (name "unconnected-(J1B-D25-Pad128)") (class "Default")
      (node (ref "J1") (pin "128") (pinfunction "D25_128") (pintype "bidirectional"))
    )
    (net (code "166") (name "unconnected-(J1B-D26-Pad129)") (class "Default")
      (node (ref "J1") (pin "129") (pinfunction "D26_129") (pintype "bidirectional"))
    )
    (net (code "167") (name "unconnected-(J1B-D27-Pad130)") (class "Default")
      (node (ref "J1") (pin "130") (pinfunction "D27_130") (pintype "bidirectional"))
    )
    (net (code "168") (name "unconnected-(J1B-D28-Pad131)") (class "Default")
      (node (ref "J1") (pin "131") (pinfunction "D28_131") (pintype "bidirectional"))
    )
    (net (code "169") (name "unconnected-(J1B-D29-Pad132)") (class "Default")
      (node (ref "J1") (pin "132") (pinfunction "D29_132") (pintype "bidirectional"))
    )
    (net (code "170") (name "unconnected-(J1B-D30-Pad133)") (class "Default")
      (node (ref "J1") (pin "133") (pinfunction "D30_133") (pintype "bidirectional"))
    )
    (net (code "171") (name "unconnected-(J1B-D31-Pad134)") (class "Default")
      (node (ref "J1") (pin "134") (pinfunction "D31_134") (pintype "bidirectional"))
    )
    (net (code "172") (name "unconnected-(J1C-+3.3V-Pad260)") (class "Default")
      (node (ref "J1") (pin "260") (pinfunction "+3.3V_260") (pintype "power_in"))
    )
    (net (code "173") (name "unconnected-(J1C-B:RX-Pad229)") (class "Default")
      (node (ref "J1") (pin "229") (pinfunction "B:RX_229") (pintype "bidirectional"))
    )
    (net (code "174") (name "unconnected-(J1C-B:TPU0-Pad223)") (class "Default")
      (node (ref "J1") (pin "223") (pinfunction "B:TPU0_223") (pintype "bidirectional"))
    )
    (net (code "175") (name "unconnected-(J1C-B:TPU1-Pad222)") (class "Default")
      (node (ref "J1") (pin "222") (pinfunction "B:TPU1_222") (pintype "bidirectional"))
    )
    (net (code "176") (name "unconnected-(J1C-B:TPU2-Pad221)") (class "Default")
      (node (ref "J1") (pin "221") (pinfunction "B:TPU2_221") (pintype "bidirectional"))
    )
    (net (code "177") (name "unconnected-(J1C-B:TPU3-Pad220)") (class "Default")
      (node (ref "J1") (pin "220") (pinfunction "B:TPU3_220") (pintype "bidirectional"))
    )
    (net (code "178") (name "unconnected-(J1C-B:TPU4-Pad219)") (class "Default")
      (node (ref "J1") (pin "219") (pinfunction "B:TPU4_219") (pintype "bidirectional"))
    )
    (net (code "179") (name "unconnected-(J1C-B:TPU5-Pad218)") (class "Default")
      (node (ref "J1") (pin "218") (pinfunction "B:TPU5_218") (pintype "bidirectional"))
    )
    (net (code "180") (name "unconnected-(J1C-B:TPU6-Pad217)") (class "Default")
      (node (ref "J1") (pin "217") (pinfunction "B:TPU6_217") (pintype "bidirectional"))
    )
    (net (code "181") (name "unconnected-(J1C-B:TPU7-Pad216)") (class "Default")
      (node (ref "J1") (pin "216") (pinfunction "B:TPU7_216") (pintype "bidirectional"))
    )
    (net (code "182") (name "unconnected-(J1C-B:TPU8-Pad215)") (class "Default")
      (node (ref "J1") (pin "215") (pinfunction "B:TPU8_215") (pintype "bidirectional"))
    )
    (net (code "183") (name "unconnected-(J1C-B:TPU9-Pad214)") (class "Default")
      (node (ref "J1") (pin "214") (pinfunction "B:TPU9_214") (pintype "bidirectional"))
    )
    (net (code "184") (name "unconnected-(J1C-B:TPU10-Pad213)") (class "Default")
      (node (ref "J1") (pin "213") (pinfunction "B:TPU10_213") (pintype "bidirectional"))
    )
    (net (code "185") (name "unconnected-(J1C-B:TPU11-Pad212)") (class "Default")
      (node (ref "J1") (pin "212") (pinfunction "B:TPU11_212") (pintype "bidirectional"))
    )
    (net (code "186") (name "unconnected-(J1C-B:TPU12-Pad211)") (class "Default")
      (node (ref "J1") (pin "211") (pinfunction "B:TPU12_211") (pintype "bidirectional"))
    )
    (net (code "187") (name "unconnected-(J1C-B:TPU13-Pad210)") (class "Default")
      (node (ref "J1") (pin "210") (pinfunction "B:TPU13_210") (pintype "bidirectional"))
    )
    (net (code "188") (name "unconnected-(J1C-B:TPU14-Pad209)") (class "Default")
      (node (ref "J1") (pin "209") (pinfunction "B:TPU14_209") (pintype "bidirectional"))
    )
    (net (code "189") (name "unconnected-(J1C-B:TPU15-Pad208)") (class "Default")
      (node (ref "J1") (pin "208") (pinfunction "B:TPU15_208") (pintype "bidirectional"))
    )
    (net (code "190") (name "unconnected-(J1C-B:TPUCLK-Pad207)") (class "Default")
      (node (ref "J1") (pin "207") (pinfunction "B:TPUCLK_207") (pintype "bidirectional"))
    )
    (net (code "191") (name "unconnected-(J1C-B:TX-Pad228)") (class "Default")
      (node (ref "J1") (pin "228") (pinfunction "B:TX_228") (pintype "bidirectional"))
    )
    (net (code "192") (name "unconnected-(J1C-BDIP-Pad254)") (class "Default")
      (node (ref "J1") (pin "254") (pinfunction "BDIP_254") (pintype "bidirectional"))
    )
    (net (code "193") (name "unconnected-(J1C-BI{slash}STS-Pad249)") (class "Default")
      (node (ref "J1") (pin "249") (pinfunction "BI/STS_249") (pintype "bidirectional"))
    )
    (net (code "194") (name "unconnected-(J1C-Burst-Pad255)") (class "Default")
      (node (ref "J1") (pin "255") (pinfunction "Burst_255") (pintype "bidirectional"))
    )
    (net (code "195") (name "unconnected-(J1C-CS2-Pad240)") (class "Default")
      (node (ref "J1") (pin "240") (pinfunction "CS2_240") (pintype "bidirectional"))
    )
    (net (code "196") (name "unconnected-(J1C-CS3-Pad239)") (class "Default")
      (node (ref "J1") (pin "239") (pinfunction "CS3_239") (pintype "bidirectional"))
    )
    (net (code "197") (name "unconnected-(J1C-ClkOut-Pad226)") (class "Default")
      (node (ref "J1") (pin "226") (pinfunction "ClkOut_226") (pintype "bidirectional"))
    )
    (net (code "198") (name "unconnected-(J1C-EngClk-Pad227)") (class "Default")
      (node (ref "J1") (pin "227") (pinfunction "EngClk_227") (pintype "bidirectional"))
    )
    (net (code "199") (name "unconnected-(J1C-IRQ0-Pad237)") (class "Default")
      (node (ref "J1") (pin "237") (pinfunction "IRQ0_237") (pintype "bidirectional"))
    )
    (net (code "200") (name "unconnected-(J1C-IRQ1-Pad236)") (class "Default")
      (node (ref "J1") (pin "236") (pinfunction "IRQ1_236") (pintype "bidirectional"))
    )
    (net (code "201") (name "unconnected-(J1C-IRQ2-Pad235)") (class "Default")
      (node (ref "J1") (pin "235") (pinfunction "IRQ2_235") (pintype "bidirectional"))
    )
    (net (code "202") (name "unconnected-(J1C-IRQ3-Pad234)") (class "Default")
      (node (ref "J1") (pin "234") (pinfunction "IRQ3_234") (pintype "bidirectional"))
    )
    (net (code "203") (name "unconnected-(J1C-IRQ4-Pad233)") (class "Default")
      (node (ref "J1") (pin "233") (pinfunction "IRQ4_233") (pintype "bidirectional"))
    )
    (net (code "204") (name "unconnected-(J1C-IRQ5-Pad232)") (class "Default")
      (node (ref "J1") (pin "232") (pinfunction "IRQ5_232") (pintype "bidirectional"))
    )
    (net (code "205") (name "unconnected-(J1C-IRQ6-Pad231)") (class "Default")
      (node (ref "J1") (pin "231") (pinfunction "IRQ6_231") (pintype "bidirectional"))
    )
    (net (code "206") (name "unconnected-(J1C-IRQ7-Pad230)") (class "Default")
      (node (ref "J1") (pin "230") (pinfunction "IRQ7_230") (pintype "bidirectional"))
    )
    (net (code "207") (name "unconnected-(J1C-IRQOUT-Pad238)") (class "Default")
      (node (ref "J1") (pin "238") (pinfunction "IRQOUT_238") (pintype "bidirectional"))
    )
    (net (code "208") (name "unconnected-(J1C-N.C.-Pad206)") (class "Default")
      (node (ref "J1") (pin "206") (pinfunction "N.C._206") (pintype "tri_state"))
    )
    (net (code "209") (name "unconnected-(J1C-N.C.-Pad224)") (class "Default")
      (node (ref "J1") (pin "224") (pinfunction "N.C._224") (pintype "tri_state"))
    )
    (net (code "210") (name "unconnected-(J1C-N.C.-Pad241)") (class "Default")
      (node (ref "J1") (pin "241") (pinfunction "N.C._241") (pintype "tri_state"))
    )
    (net (code "211") (name "unconnected-(J1C-N.C.-Pad242)") (class "Default")
      (node (ref "J1") (pin "242") (pinfunction "N.C._242") (pintype "tri_state"))
    )
    (net (code "212") (name "unconnected-(J1C-N.C.-Pad243)") (class "Default")
      (node (ref "J1") (pin "243") (pinfunction "N.C._243") (pintype "tri_state"))
    )
    (net (code "213") (name "unconnected-(J1C-N.C.-Pad248)") (class "Default")
      (node (ref "J1") (pin "248") (pinfunction "N.C._248") (pintype "tri_state"))
    )
    (net (code "214") (name "unconnected-(J1C-OE-Pad250)") (class "Default")
      (node (ref "J1") (pin "250") (pinfunction "OE_250") (pintype "bidirectional"))
    )
    (net (code "215") (name "unconnected-(J1C-RD{slash}WR-Pad256)") (class "Default")
      (node (ref "J1") (pin "256") (pinfunction "RD/WR_256") (pintype "bidirectional"))
    )
    (net (code "216") (name "unconnected-(J1C-RXD1-Pad245)") (class "Default")
      (node (ref "J1") (pin "245") (pinfunction "RXD1_245") (pintype "bidirectional"))
    )
    (net (code "217") (name "unconnected-(J1C-TA-Pad252)") (class "Default")
      (node (ref "J1") (pin "252") (pinfunction "TA_252") (pintype "bidirectional"))
    )
    (net (code "218") (name "unconnected-(J1C-TEA-Pad251)") (class "Default")
      (node (ref "J1") (pin "251") (pinfunction "TEA_251") (pintype "bidirectional"))
    )
    (net (code "219") (name "unconnected-(J1C-TS-Pad253)") (class "Default")
      (node (ref "J1") (pin "253") (pinfunction "TS_253") (pintype "bidirectional"))
    )
    (net (code "220") (name "unconnected-(J1C-TSIZ0-Pad258)") (class "Default")
      (node (ref "J1") (pin "258") (pinfunction "TSIZ0_258") (pintype "bidirectional"))
    )
    (net (code "221") (name "unconnected-(J1C-TSIZ1-Pad257)") (class "Default")
      (node (ref "J1") (pin "257") (pinfunction "TSIZ1_257") (pintype "bidirectional"))
    )
    (net (code "222") (name "unconnected-(J1C-TXD1-Pad247)") (class "Default")
      (node (ref "J1") (pin "247") (pinfunction "TXD1_247") (pintype "bidirectional"))
    )
    (net (code "223") (name "unconnected-(P209-Pad3)") (class "Default")
      (node (ref "P209") (pin "3") (pinfunction "3_3") (pintype "passive+no_connect"))
    )
    (net (code "224") (name "unconnected-(P209-Pad4)") (class "Default")
      (node (ref "P209") (pin "4") (pinfunction "4_4") (pintype "passive+no_connect"))
    )
    (net (code "225") (name "unconnected-(P209-Pad5)") (class "Default")
      (node (ref "P209") (pin "5") (pinfunction "5_5") (pintype "passive+no_connect"))
    )
  )
)
